# senseye-2.net
KiCad netlist of a schematic drawn in EAGLE
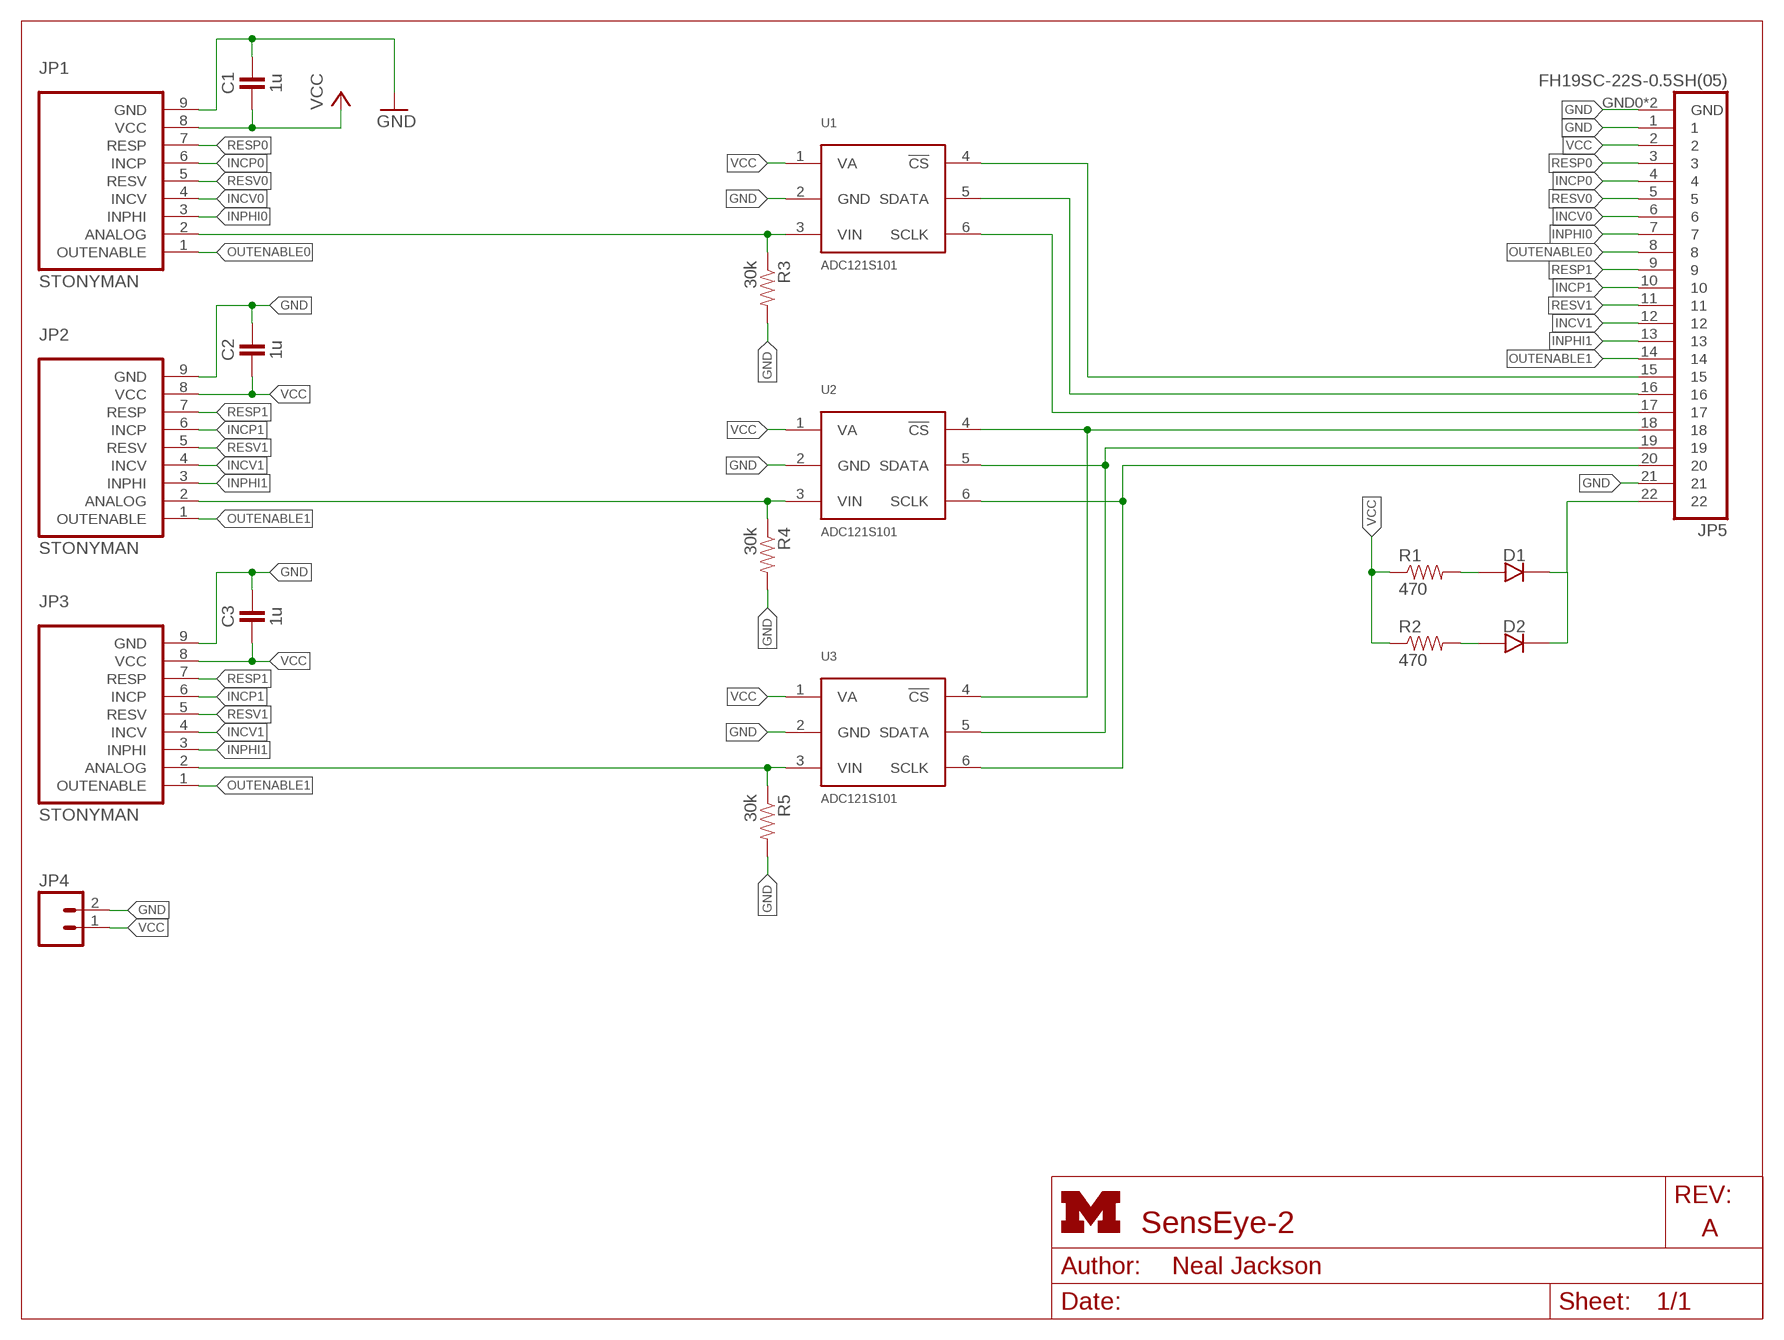
[diagram p0: schematic, sheet 1]

(export (version "E")
  (design (tool "Eeschema 10.0.6"))
  (components
    (comp (ref "C1")
      (value "1u")
      (footprint "eagle-import:0402_CAP")
      (libsource (lib "eagle-import") (part "CAPACITOR"))
    )
    (comp (ref "C2")
      (value "1u")
      (footprint "eagle-import:0402_CAP")
      (libsource (lib "eagle-import") (part "CAPACITOR"))
    )
    (comp (ref "C3")
      (value "1u")
      (footprint "eagle-import:0402_CAP")
      (libsource (lib "eagle-import") (part "CAPACITOR"))
    )
    (comp (ref "D1")
      (value "DIODE0603")
      (footprint "eagle-import:0603-DIODE")
      (libsource (lib "eagle-import") (part "DIODE0603"))
    )
    (comp (ref "D2")
      (value "DIODE0603")
      (footprint "eagle-import:0603-DIODE")
      (libsource (lib "eagle-import") (part "DIODE0603"))
    )
    (comp (ref "JP1")
      (value "STONYMAN")
      (footprint "eagle-import:1X09")
      (libsource (lib "eagle-import") (part "STONYMAN"))
    )
    (comp (ref "JP2")
      (value "STONYMAN")
      (footprint "eagle-import:1X09")
      (libsource (lib "eagle-import") (part "STONYMAN"))
    )
    (comp (ref "JP3")
      (value "STONYMAN")
      (footprint "eagle-import:1X09")
      (libsource (lib "eagle-import") (part "STONYMAN"))
    )
    (comp (ref "JP4")
      (value "M02PTH")
      (footprint "eagle-import:1X02")
      (libsource (lib "eagle-import") (part "M02PTH"))
    )
    (comp (ref "JP5")
      (value "FH19SC-22S-0.5SH(05)")
      (footprint "eagle-import:FH19SC-22S-0.5SH(05)")
      (libsource (lib "eagle-import") (part "FH19SC-22S-0.5SH(05)"))
    )
    (comp (ref "R1")
      (value "470")
      (footprint "eagle-import:0402_RES")
      (libsource (lib "eagle-import") (part "RESISTOR0402_RES"))
    )
    (comp (ref "R2")
      (value "470")
      (footprint "eagle-import:0402_RES")
      (libsource (lib "eagle-import") (part "RESISTOR0402_RES"))
    )
    (comp (ref "R3")
      (value "30k")
      (footprint "eagle-import:0402_RES")
      (libsource (lib "eagle-import") (part "RESISTOR0402_RES"))
    )
    (comp (ref "R4")
      (value "30k")
      (footprint "eagle-import:0402_RES")
      (libsource (lib "eagle-import") (part "RESISTOR0402_RES"))
    )
    (comp (ref "R5")
      (value "30k")
      (footprint "eagle-import:0402_RES")
      (libsource (lib "eagle-import") (part "RESISTOR0402_RES"))
    )
    (comp (ref "U1")
      (value "ADC121S101")
      (footprint "eagle-import:SOT-23-6")
      (libsource (lib "eagle-import") (part "ADC121S101"))
    )
    (comp (ref "U2")
      (value "ADC121S101")
      (footprint "eagle-import:SOT-23-6")
      (libsource (lib "eagle-import") (part "ADC121S101"))
    )
    (comp (ref "U3")
      (value "ADC121S101")
      (footprint "eagle-import:SOT-23-6")
      (libsource (lib "eagle-import") (part "ADC121S101"))
    )
  )
  (nets
    (net (code "1") (name "GND") (class "Default")
      (node (ref "C1") (pin "1") (pinfunction "1_1") (pintype "bidirectional"))
      (node (ref "C2") (pin "1") (pinfunction "1_1") (pintype "bidirectional"))
      (node (ref "C3") (pin "1") (pinfunction "1_1") (pintype "bidirectional"))
      (node (ref "JP1") (pin "9") (pinfunction "GND_9") (pintype "passive"))
      (node (ref "JP2") (pin "9") (pinfunction "GND_9") (pintype "passive"))
      (node (ref "JP3") (pin "9") (pinfunction "GND_9") (pintype "passive"))
      (node (ref "JP4") (pin "2") (pinfunction "2_2") (pintype "passive"))
      (node (ref "JP5") (pin "1") (pinfunction "1_1") (pintype "passive"))
      (node (ref "JP5") (pin "21") (pinfunction "21_21") (pintype "passive"))
      (node (ref "JP5") (pin "GND0") (pinfunction "GND_GND0") (pintype "bidirectional"))
      (node (ref "JP5") (pin "GND1") (pinfunction "GND_GND1") (pintype "bidirectional"))
      (node (ref "R3") (pin "2") (pinfunction "2_2") (pintype "passive"))
      (node (ref "R4") (pin "2") (pinfunction "2_2") (pintype "passive"))
      (node (ref "R5") (pin "2") (pinfunction "2_2") (pintype "passive"))
      (node (ref "U1") (pin "2") (pinfunction "GND_2") (pintype "bidirectional"))
      (node (ref "U2") (pin "2") (pinfunction "GND_2") (pintype "bidirectional"))
      (node (ref "U3") (pin "2") (pinfunction "GND_2") (pintype "bidirectional"))
    )
    (net (code "2") (name "INCP0") (class "Default")
      (node (ref "JP1") (pin "6") (pinfunction "INCP_6") (pintype "passive"))
      (node (ref "JP5") (pin "4") (pinfunction "4_4") (pintype "passive"))
    )
    (net (code "3") (name "INCP1") (class "Default")
      (node (ref "JP2") (pin "6") (pinfunction "INCP_6") (pintype "passive"))
      (node (ref "JP3") (pin "6") (pinfunction "INCP_6") (pintype "passive"))
      (node (ref "JP5") (pin "10") (pinfunction "10_10") (pintype "passive"))
    )
    (net (code "4") (name "INCV0") (class "Default")
      (node (ref "JP1") (pin "4") (pinfunction "INCV_4") (pintype "passive"))
      (node (ref "JP5") (pin "6") (pinfunction "6_6") (pintype "passive"))
    )
    (net (code "5") (name "INCV1") (class "Default")
      (node (ref "JP2") (pin "4") (pinfunction "INCV_4") (pintype "passive"))
      (node (ref "JP3") (pin "4") (pinfunction "INCV_4") (pintype "passive"))
      (node (ref "JP5") (pin "12") (pinfunction "12_12") (pintype "passive"))
    )
    (net (code "6") (name "INPHI0") (class "Default")
      (node (ref "JP1") (pin "3") (pinfunction "INPHI_3") (pintype "passive"))
      (node (ref "JP5") (pin "7") (pinfunction "7_7") (pintype "passive"))
    )
    (net (code "7") (name "INPHI1") (class "Default")
      (node (ref "JP2") (pin "3") (pinfunction "INPHI_3") (pintype "passive"))
      (node (ref "JP3") (pin "3") (pinfunction "INPHI_3") (pintype "passive"))
      (node (ref "JP5") (pin "13") (pinfunction "13_13") (pintype "passive"))
    )
    (net (code "8") (name "Net-(D1-ANODE)") (class "Default")
      (node (ref "D1") (pin "1") (pinfunction "ANODE_1") (pintype "bidirectional"))
      (node (ref "R1") (pin "2") (pinfunction "2_2") (pintype "passive"))
    )
    (net (code "9") (name "Net-(D1-CATHODE)") (class "Default")
      (node (ref "D1") (pin "2") (pinfunction "CATHODE_2") (pintype "bidirectional"))
      (node (ref "D2") (pin "2") (pinfunction "CATHODE_2") (pintype "bidirectional"))
      (node (ref "JP5") (pin "22") (pinfunction "22_22") (pintype "passive"))
    )
    (net (code "10") (name "Net-(D2-ANODE)") (class "Default")
      (node (ref "D2") (pin "1") (pinfunction "ANODE_1") (pintype "bidirectional"))
      (node (ref "R2") (pin "2") (pinfunction "2_2") (pintype "passive"))
    )
    (net (code "11") (name "Net-(JP1-ANALOG)") (class "Default")
      (node (ref "JP1") (pin "2") (pinfunction "ANALOG_2") (pintype "passive"))
      (node (ref "R3") (pin "1") (pinfunction "1_1") (pintype "passive"))
      (node (ref "U1") (pin "3") (pinfunction "VIN_3") (pintype "bidirectional"))
    )
    (net (code "12") (name "Net-(JP2-ANALOG)") (class "Default")
      (node (ref "JP2") (pin "2") (pinfunction "ANALOG_2") (pintype "passive"))
      (node (ref "R4") (pin "1") (pinfunction "1_1") (pintype "passive"))
      (node (ref "U2") (pin "3") (pinfunction "VIN_3") (pintype "bidirectional"))
    )
    (net (code "13") (name "Net-(JP3-ANALOG)") (class "Default")
      (node (ref "JP3") (pin "2") (pinfunction "ANALOG_2") (pintype "passive"))
      (node (ref "R5") (pin "1") (pinfunction "1_1") (pintype "passive"))
      (node (ref "U3") (pin "3") (pinfunction "VIN_3") (pintype "bidirectional"))
    )
    (net (code "14") (name "Net-(U1-SCLK)") (class "Default")
      (node (ref "JP5") (pin "17") (pinfunction "17_17") (pintype "passive"))
      (node (ref "U1") (pin "6") (pinfunction "SCLK_6") (pintype "bidirectional"))
    )
    (net (code "15") (name "Net-(U1-SDATA)") (class "Default")
      (node (ref "JP5") (pin "16") (pinfunction "16_16") (pintype "passive"))
      (node (ref "U1") (pin "5") (pinfunction "SDATA_5") (pintype "bidirectional"))
    )
    (net (code "16") (name "Net-(U1-~{CS})") (class "Default")
      (node (ref "JP5") (pin "15") (pinfunction "15_15") (pintype "passive"))
      (node (ref "U1") (pin "4") (pinfunction "~{CS}_4") (pintype "bidirectional"))
    )
    (net (code "17") (name "Net-(U2-SCLK)") (class "Default")
      (node (ref "JP5") (pin "20") (pinfunction "20_20") (pintype "passive"))
      (node (ref "U2") (pin "6") (pinfunction "SCLK_6") (pintype "bidirectional"))
      (node (ref "U3") (pin "6") (pinfunction "SCLK_6") (pintype "bidirectional"))
    )
    (net (code "18") (name "Net-(U2-SDATA)") (class "Default")
      (node (ref "JP5") (pin "19") (pinfunction "19_19") (pintype "passive"))
      (node (ref "U2") (pin "5") (pinfunction "SDATA_5") (pintype "bidirectional"))
      (node (ref "U3") (pin "5") (pinfunction "SDATA_5") (pintype "bidirectional"))
    )
    (net (code "19") (name "Net-(U2-~{CS})") (class "Default")
      (node (ref "JP5") (pin "18") (pinfunction "18_18") (pintype "passive"))
      (node (ref "U2") (pin "4") (pinfunction "~{CS}_4") (pintype "bidirectional"))
      (node (ref "U3") (pin "4") (pinfunction "~{CS}_4") (pintype "bidirectional"))
    )
    (net (code "20") (name "OUTENABLE0") (class "Default")
      (node (ref "JP1") (pin "1") (pinfunction "OUTENABLE_1") (pintype "passive"))
      (node (ref "JP5") (pin "8") (pinfunction "8_8") (pintype "passive"))
    )
    (net (code "21") (name "OUTENABLE1") (class "Default")
      (node (ref "JP2") (pin "1") (pinfunction "OUTENABLE_1") (pintype "passive"))
      (node (ref "JP3") (pin "1") (pinfunction "OUTENABLE_1") (pintype "passive"))
      (node (ref "JP5") (pin "14") (pinfunction "14_14") (pintype "passive"))
    )
    (net (code "22") (name "RESP0") (class "Default")
      (node (ref "JP1") (pin "7") (pinfunction "RESP_7") (pintype "passive"))
      (node (ref "JP5") (pin "3") (pinfunction "3_3") (pintype "passive"))
    )
    (net (code "23") (name "RESP1") (class "Default")
      (node (ref "JP2") (pin "7") (pinfunction "RESP_7") (pintype "passive"))
      (node (ref "JP3") (pin "7") (pinfunction "RESP_7") (pintype "passive"))
      (node (ref "JP5") (pin "9") (pinfunction "9_9") (pintype "passive"))
    )
    (net (code "24") (name "RESV0") (class "Default")
      (node (ref "JP1") (pin "5") (pinfunction "RESV_5") (pintype "passive"))
      (node (ref "JP5") (pin "5") (pinfunction "5_5") (pintype "passive"))
    )
    (net (code "25") (name "RESV1") (class "Default")
      (node (ref "JP2") (pin "5") (pinfunction "RESV_5") (pintype "passive"))
      (node (ref "JP3") (pin "5") (pinfunction "RESV_5") (pintype "passive"))
      (node (ref "JP5") (pin "11") (pinfunction "11_11") (pintype "passive"))
    )
    (net (code "26") (name "VCC") (class "Default")
      (node (ref "C1") (pin "2") (pinfunction "2_2") (pintype "bidirectional"))
      (node (ref "C2") (pin "2") (pinfunction "2_2") (pintype "bidirectional"))
      (node (ref "C3") (pin "2") (pinfunction "2_2") (pintype "bidirectional"))
      (node (ref "JP1") (pin "8") (pinfunction "VCC_8") (pintype "passive"))
      (node (ref "JP2") (pin "8") (pinfunction "VCC_8") (pintype "passive"))
      (node (ref "JP3") (pin "8") (pinfunction "VCC_8") (pintype "passive"))
      (node (ref "JP4") (pin "1") (pinfunction "1_1") (pintype "passive"))
      (node (ref "JP5") (pin "2") (pinfunction "2_2") (pintype "passive"))
      (node (ref "R1") (pin "1") (pinfunction "1_1") (pintype "passive"))
      (node (ref "R2") (pin "1") (pinfunction "1_1") (pintype "passive"))
      (node (ref "U1") (pin "1") (pinfunction "VA_1") (pintype "bidirectional"))
      (node (ref "U2") (pin "1") (pinfunction "VA_1") (pintype "bidirectional"))
      (node (ref "U3") (pin "1") (pinfunction "VA_1") (pintype "bidirectional"))
    )
  )
)
